# 01-Breadboard.net
KiCad netlist of a schematic drawn in Altium Designer
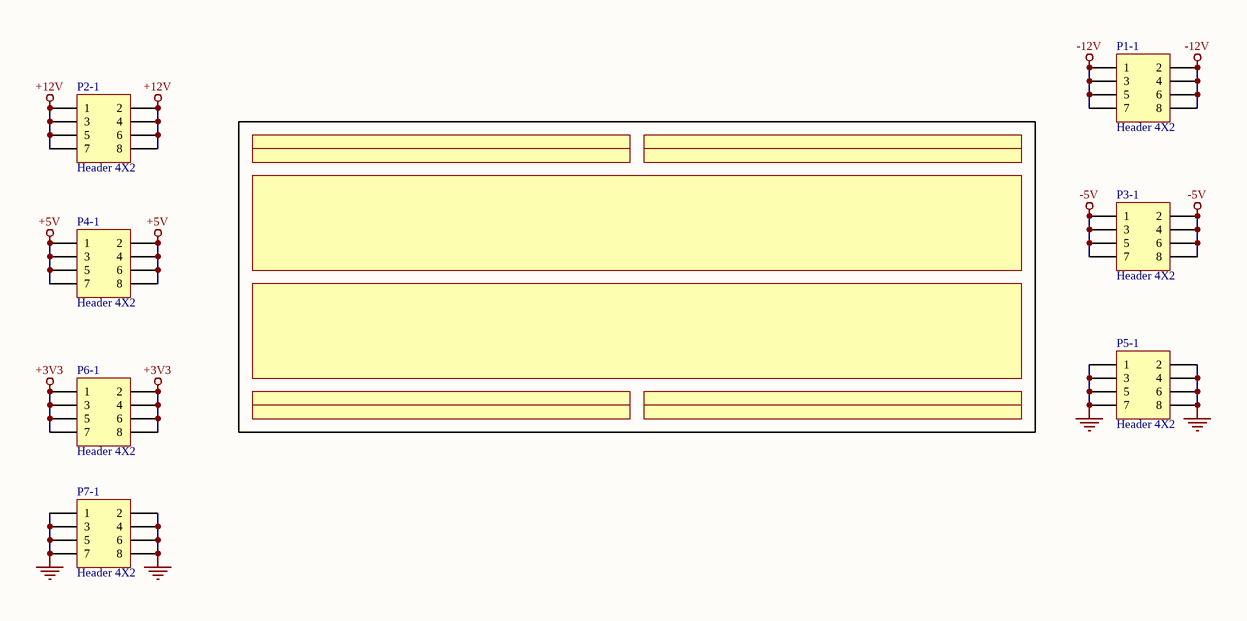
[diagram p0: 01-Breadboard.SchDoc]

(export (version "E")
  (design (tool "Eeschema 10.0.6"))
  (components
    (comp (ref "P1-1")
      (value "Header 4X2")
      (footprint "JP2.54-F-2x04A")
      (description "Header, 4-Pin, Dual row")
      (fields (field (name "PUBLISHER") "Altium Limited"))
      (libsource (lib "Miscellaneous Connectors") (part "Header 4X2"))
    )
    (comp (ref "P2-1")
      (value "Header 4X2")
      (footprint "JP2.54-F-2x04A")
      (description "Header, 4-Pin, Dual row")
      (fields (field (name "PUBLISHER") "Altium Limited"))
      (libsource (lib "Miscellaneous Connectors") (part "Header 4X2"))
    )
    (comp (ref "P3-1")
      (value "Header 4X2")
      (footprint "JP2.54-F-2x04A")
      (description "Header, 4-Pin, Dual row")
      (fields (field (name "PUBLISHER") "Altium Limited"))
      (libsource (lib "Miscellaneous Connectors") (part "Header 4X2"))
    )
    (comp (ref "P4-1")
      (value "Header 4X2")
      (footprint "JP2.54-F-2x04A")
      (description "Header, 4-Pin, Dual row")
      (fields (field (name "PUBLISHER") "Altium Limited"))
      (libsource (lib "Miscellaneous Connectors") (part "Header 4X2"))
    )
    (comp (ref "P5-1")
      (value "Header 4X2")
      (footprint "JP2.54-F-2x04A")
      (description "Header, 4-Pin, Dual row")
      (fields (field (name "PUBLISHER") "Altium Limited"))
      (libsource (lib "Miscellaneous Connectors") (part "Header 4X2"))
    )
    (comp (ref "P6-1")
      (value "Header 4X2")
      (footprint "JP2.54-F-2x04A")
      (description "Header, 4-Pin, Dual row")
      (fields (field (name "PUBLISHER") "Altium Limited"))
      (libsource (lib "Miscellaneous Connectors") (part "Header 4X2"))
    )
    (comp (ref "P7-1")
      (value "Header 4X2")
      (footprint "JP2.54-F-2x04A")
      (description "Header, 4-Pin, Dual row")
      (fields (field (name "PUBLISHER") "Altium Limited"))
      (libsource (lib "Miscellaneous Connectors") (part "Header 4X2"))
    )
  )
  (nets
    (net (code "1") (name "+3V3") (class "Default")
      (node (ref "P6-1") (pin "1") (pinfunction "1_1") (pintype "passive"))
      (node (ref "P6-1") (pin "2") (pinfunction "2_2") (pintype "passive"))
      (node (ref "P6-1") (pin "3") (pinfunction "3_3") (pintype "passive"))
      (node (ref "P6-1") (pin "4") (pinfunction "4_4") (pintype "passive"))
      (node (ref "P6-1") (pin "5") (pinfunction "5_5") (pintype "passive"))
      (node (ref "P6-1") (pin "6") (pinfunction "6_6") (pintype "passive"))
      (node (ref "P6-1") (pin "7") (pinfunction "7_7") (pintype "passive"))
      (node (ref "P6-1") (pin "8") (pinfunction "8_8") (pintype "passive"))
    )
    (net (code "2") (name "+5V") (class "Default")
      (node (ref "P4-1") (pin "1") (pinfunction "1_1") (pintype "passive"))
      (node (ref "P4-1") (pin "2") (pinfunction "2_2") (pintype "passive"))
      (node (ref "P4-1") (pin "3") (pinfunction "3_3") (pintype "passive"))
      (node (ref "P4-1") (pin "4") (pinfunction "4_4") (pintype "passive"))
      (node (ref "P4-1") (pin "5") (pinfunction "5_5") (pintype "passive"))
      (node (ref "P4-1") (pin "6") (pinfunction "6_6") (pintype "passive"))
      (node (ref "P4-1") (pin "7") (pinfunction "7_7") (pintype "passive"))
      (node (ref "P4-1") (pin "8") (pinfunction "8_8") (pintype "passive"))
    )
    (net (code "3") (name "+12V") (class "Default")
      (node (ref "P2-1") (pin "1") (pinfunction "1_1") (pintype "passive"))
      (node (ref "P2-1") (pin "2") (pinfunction "2_2") (pintype "passive"))
      (node (ref "P2-1") (pin "3") (pinfunction "3_3") (pintype "passive"))
      (node (ref "P2-1") (pin "4") (pinfunction "4_4") (pintype "passive"))
      (node (ref "P2-1") (pin "5") (pinfunction "5_5") (pintype "passive"))
      (node (ref "P2-1") (pin "6") (pinfunction "6_6") (pintype "passive"))
      (node (ref "P2-1") (pin "7") (pinfunction "7_7") (pintype "passive"))
      (node (ref "P2-1") (pin "8") (pinfunction "8_8") (pintype "passive"))
    )
    (net (code "4") (name "-5V") (class "Default")
      (node (ref "P3-1") (pin "1") (pinfunction "1_1") (pintype "passive"))
      (node (ref "P3-1") (pin "2") (pinfunction "2_2") (pintype "passive"))
      (node (ref "P3-1") (pin "3") (pinfunction "3_3") (pintype "passive"))
      (node (ref "P3-1") (pin "4") (pinfunction "4_4") (pintype "passive"))
      (node (ref "P3-1") (pin "5") (pinfunction "5_5") (pintype "passive"))
      (node (ref "P3-1") (pin "6") (pinfunction "6_6") (pintype "passive"))
      (node (ref "P3-1") (pin "7") (pinfunction "7_7") (pintype "passive"))
      (node (ref "P3-1") (pin "8") (pinfunction "8_8") (pintype "passive"))
    )
    (net (code "5") (name "-12V") (class "Default")
      (node (ref "P1-1") (pin "1") (pinfunction "1_1") (pintype "passive"))
      (node (ref "P1-1") (pin "2") (pinfunction "2_2") (pintype "passive"))
      (node (ref "P1-1") (pin "3") (pinfunction "3_3") (pintype "passive"))
      (node (ref "P1-1") (pin "4") (pinfunction "4_4") (pintype "passive"))
      (node (ref "P1-1") (pin "5") (pinfunction "5_5") (pintype "passive"))
      (node (ref "P1-1") (pin "6") (pinfunction "6_6") (pintype "passive"))
      (node (ref "P1-1") (pin "7") (pinfunction "7_7") (pintype "passive"))
      (node (ref "P1-1") (pin "8") (pinfunction "8_8") (pintype "passive"))
    )
    (net (code "6") (name "GND") (class "Default")
      (node (ref "P5-1") (pin "1") (pinfunction "1_1") (pintype "passive"))
      (node (ref "P5-1") (pin "2") (pinfunction "2_2") (pintype "passive"))
      (node (ref "P5-1") (pin "3") (pinfunction "3_3") (pintype "passive"))
      (node (ref "P5-1") (pin "4") (pinfunction "4_4") (pintype "passive"))
      (node (ref "P5-1") (pin "5") (pinfunction "5_5") (pintype "passive"))
      (node (ref "P5-1") (pin "6") (pinfunction "6_6") (pintype "passive"))
      (node (ref "P5-1") (pin "7") (pinfunction "7_7") (pintype "passive"))
      (node (ref "P5-1") (pin "8") (pinfunction "8_8") (pintype "passive"))
      (node (ref "P7-1") (pin "1") (pinfunction "1_1") (pintype "passive"))
      (node (ref "P7-1") (pin "2") (pinfunction "2_2") (pintype "passive"))
      (node (ref "P7-1") (pin "3") (pinfunction "3_3") (pintype "passive"))
      (node (ref "P7-1") (pin "4") (pinfunction "4_4") (pintype "passive"))
      (node (ref "P7-1") (pin "5") (pinfunction "5_5") (pintype "passive"))
      (node (ref "P7-1") (pin "6") (pinfunction "6_6") (pintype "passive"))
      (node (ref "P7-1") (pin "7") (pinfunction "7_7") (pintype "passive"))
      (node (ref "P7-1") (pin "8") (pinfunction "8_8") (pintype "passive"))
    )
  )
)
